# multimeter.net
KiCad netlist of a schematic drawn in EAGLE
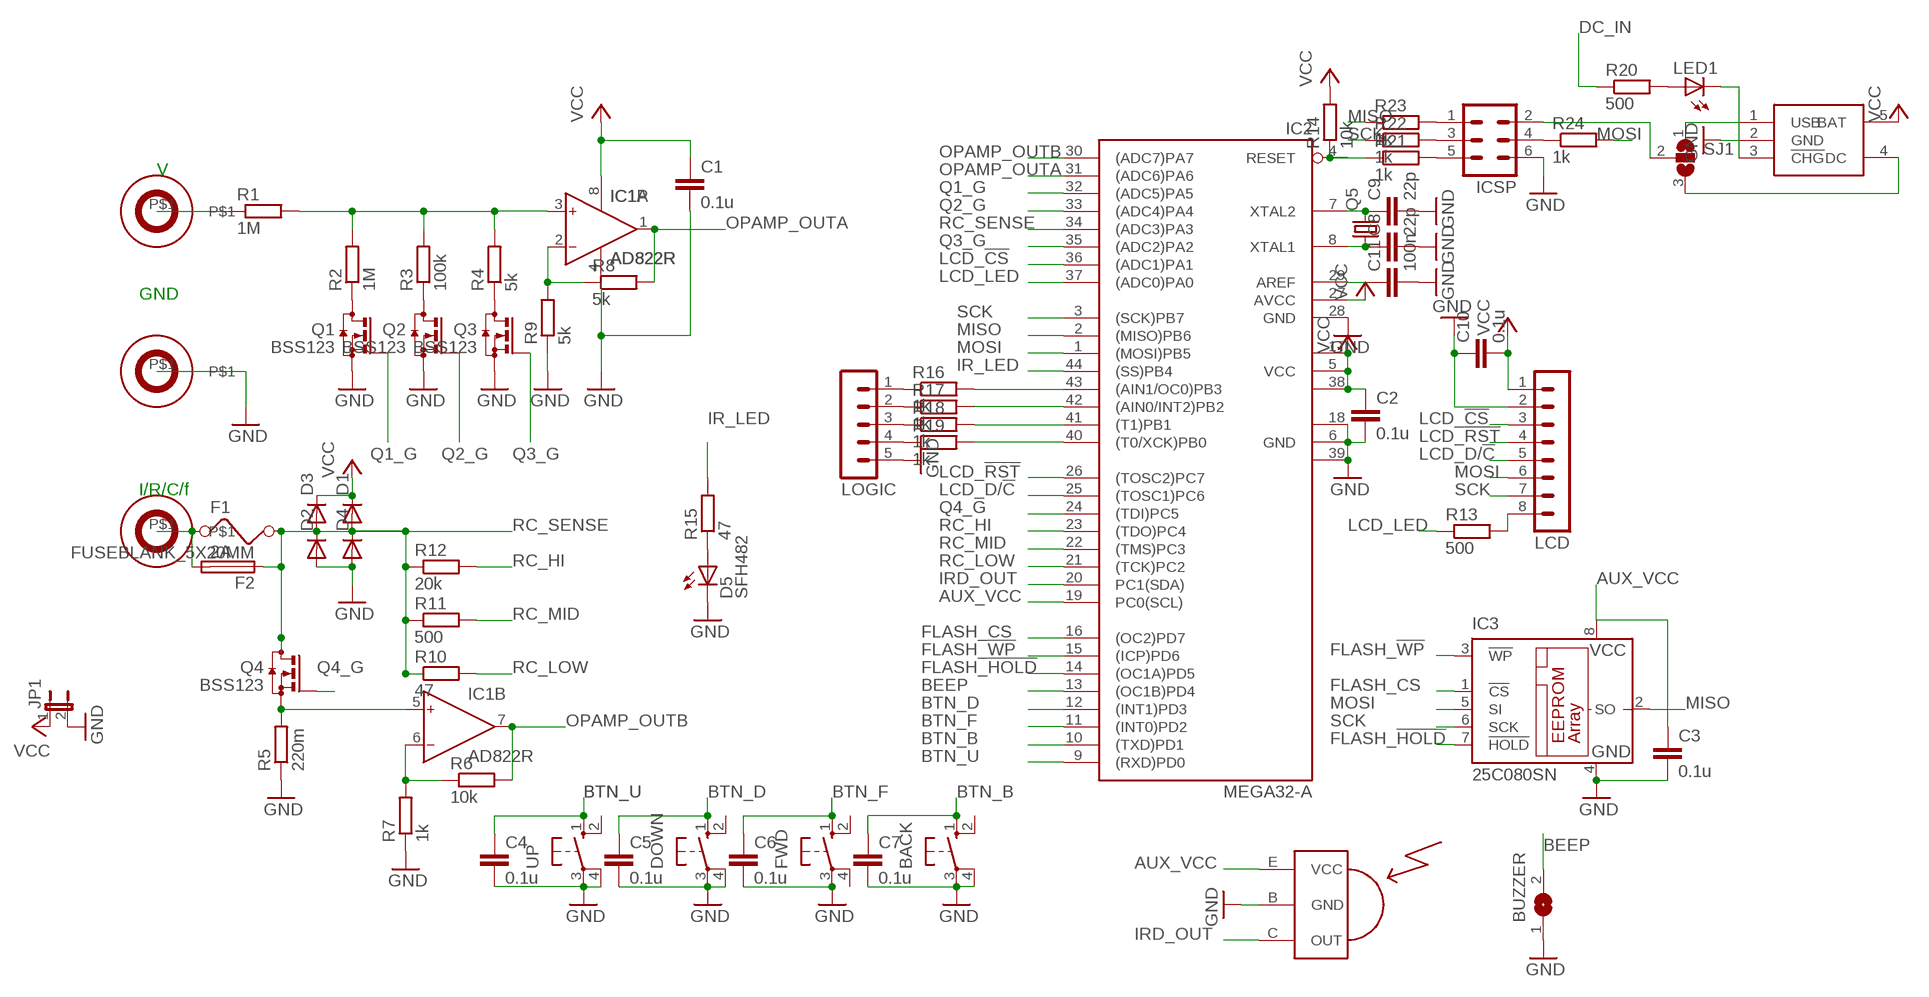
[diagram p0: schematic, sheet 1]

(export (version "E")
  (design (tool "Eeschema 10.0.6"))
  (components
    (comp (ref "BACK")
      (value "10-XX")
      (footprint "eagle-import:B3F-10XX")
      (fields (field (name "MPN") "B3F-1000"))
      (libsource (lib "eagle-import") (part "10-XX"))
    )
    (comp (ref "BUZZER")
      (value "SJW")
      (footprint "eagle-import:SJW")
      (libsource (lib "eagle-import") (part "SJW"))
    )
    (comp (ref "C1")
      (value "0.1u")
      (footprint "eagle-import:C0805")
      (libsource (lib "eagle-import") (part "C-EUC0805"))
    )
    (comp (ref "C2")
      (value "0.1u")
      (footprint "eagle-import:C0805")
      (libsource (lib "eagle-import") (part "C-EUC0805"))
    )
    (comp (ref "C3")
      (value "0.1u")
      (footprint "eagle-import:C0805")
      (libsource (lib "eagle-import") (part "C-EUC0805"))
    )
    (comp (ref "C4")
      (value "0.1u")
      (footprint "eagle-import:C0805")
      (libsource (lib "eagle-import") (part "C-EUC0805"))
    )
    (comp (ref "C5")
      (value "0.1u")
      (footprint "eagle-import:C0805")
      (libsource (lib "eagle-import") (part "C-EUC0805"))
    )
    (comp (ref "C6")
      (value "0.1u")
      (footprint "eagle-import:C0805")
      (libsource (lib "eagle-import") (part "C-EUC0805"))
    )
    (comp (ref "C7")
      (value "0.1u")
      (footprint "eagle-import:C0805")
      (libsource (lib "eagle-import") (part "C-EUC0805"))
    )
    (comp (ref "C8")
      (value "22p")
      (footprint "eagle-import:C0603")
      (libsource (lib "eagle-import") (part "C-EUC0603"))
    )
    (comp (ref "C9")
      (value "22p")
      (footprint "eagle-import:C0603")
      (libsource (lib "eagle-import") (part "C-EUC0603"))
    )
    (comp (ref "C10")
      (value "0.1u")
      (footprint "eagle-import:C0805")
      (libsource (lib "eagle-import") (part "C-EUC0805"))
    )
    (comp (ref "C11")
      (value "100n")
      (footprint "eagle-import:C0805")
      (libsource (lib "eagle-import") (part "C-EUC0805"))
    )
    (comp (ref "D1")
      (value "DIODE-SOD123")
      (footprint "eagle-import:SOD123")
      (libsource (lib "eagle-import") (part "DIODE-SOD123"))
    )
    (comp (ref "D2")
      (value "DIODE-SOD123")
      (footprint "eagle-import:SOD123")
      (libsource (lib "eagle-import") (part "DIODE-SOD123"))
    )
    (comp (ref "D3")
      (value "DIODE-SOD123")
      (footprint "eagle-import:SOD123")
      (libsource (lib "eagle-import") (part "DIODE-SOD123"))
    )
    (comp (ref "D4")
      (value "DIODE-SOD123")
      (footprint "eagle-import:SOD123")
      (libsource (lib "eagle-import") (part "DIODE-SOD123"))
    )
    (comp (ref "D5")
      (value "SFH482")
      (footprint "eagle-import:SFH482")
      (libsource (lib "eagle-import") (part "SFH482"))
    )
    (comp (ref "DOWN")
      (value "10-XX")
      (footprint "eagle-import:B3F-10XX")
      (fields (field (name "MPN") "B3F-1000"))
      (libsource (lib "eagle-import") (part "10-XX"))
    )
    (comp (ref "F1")
      (value "2A")
      (footprint "eagle-import:R1206")
      (libsource (lib "eagle-import") (part "FUSE'1206'"))
    )
    (comp (ref "F2")
      (value "FUSEBLANK_5X20MM")
      (footprint "eagle-import:FUSE_HOLDER_5X20MM")
      (libsource (lib "eagle-import") (part "FUSEBLANK_5X20MM"))
    )
    (comp (ref "FWD")
      (value "10-XX")
      (footprint "eagle-import:B3F-10XX")
      (fields (field (name "MPN") "B3F-1000"))
      (libsource (lib "eagle-import") (part "10-XX"))
    )
    (comp (ref "IC1")
      (value "AD822R")
      (footprint "eagle-import:SO8")
      (fields (field (name "MF") "ANALOG DEVICES") (field (name "MPN") "AD822BRZ"))
      (libsource (lib "eagle-import") (part "AD822R"))
    )
    (comp (ref "IC2")
      (value "MEGA32-A")
      (footprint "eagle-import:TQFP44")
      (fields (field (name "MPN") "ATMEGA32-16AU"))
      (libsource (lib "eagle-import") (part "MEGA32-A"))
    )
    (comp (ref "IC3")
      (value "25C080SN")
      (footprint "eagle-import:SO-08")
      (fields (field (name "MF") "MICROCHIP") (field (name "MPN") "25C080/SN"))
      (libsource (lib "eagle-import") (part "25SNC080"))
    )
    (comp (ref "ICSP")
      (value "MA03-2")
      (footprint "eagle-import:MA03-2")
      (libsource (lib "eagle-import") (part "MA03-2"))
    )
    (comp (ref "JP1")
      (value "JP1E")
      (footprint "eagle-import:JP1")
      (libsource (lib "eagle-import") (part "JP1E"))
    )
    (comp (ref "LCD")
      (value "MA08-1")
      (footprint "eagle-import:MA08-1")
      (libsource (lib "eagle-import") (part "MA08-1"))
    )
    (comp (ref "LED1")
      (value "LEDSML0805")
      (footprint "eagle-import:SML0805")
      (libsource (lib "eagle-import") (part "LEDSML0805"))
    )
    (comp (ref "LOGIC")
      (value "MA05-1")
      (footprint "eagle-import:MA05-1")
      (libsource (lib "eagle-import") (part "MA05-1"))
    )
    (comp (ref "N$36")
      (value "BINDINGPOST4MMPCB")
      (footprint "eagle-import:BINDINGPOSTPCB")
      (libsource (lib "eagle-import") (part "BINDINGPOST4MMPCB"))
    )
    (comp (ref "Q1")
      (value "BSS123")
      (footprint "eagle-import:SOT23")
      (libsource (lib "eagle-import") (part "BSS123"))
    )
    (comp (ref "Q2")
      (value "BSS123")
      (footprint "eagle-import:SOT23")
      (libsource (lib "eagle-import") (part "BSS123"))
    )
    (comp (ref "Q3")
      (value "BSS123")
      (footprint "eagle-import:SOT23")
      (libsource (lib "eagle-import") (part "BSS123"))
    )
    (comp (ref "Q4")
      (value "BSS123")
      (footprint "eagle-import:SOT23")
      (libsource (lib "eagle-import") (part "BSS123"))
    )
    (comp (ref "Q5")
      (value "CRYSTALHC49UP")
      (footprint "eagle-import:HC49UP")
      (libsource (lib "eagle-import") (part "CRYSTALHC49UP"))
    )
    (comp (ref "R1")
      (value "1M")
      (footprint "eagle-import:0207_12")
      (libsource (lib "eagle-import") (part "R-EU_0207/12"))
    )
    (comp (ref "R2")
      (value "1M")
      (footprint "eagle-import:R0805")
      (libsource (lib "eagle-import") (part "resistor_R-EU_R0805"))
    )
    (comp (ref "R3")
      (value "100k")
      (footprint "eagle-import:R0805")
      (libsource (lib "eagle-import") (part "resistor_R-EU_R0805"))
    )
    (comp (ref "R4")
      (value "5k")
      (footprint "eagle-import:R0805")
      (libsource (lib "eagle-import") (part "resistor_R-EU_R0805"))
    )
    (comp (ref "R5")
      (value "220m")
      (footprint "eagle-import:R1206")
      (libsource (lib "eagle-import") (part "resistor_R-EU_R1206"))
    )
    (comp (ref "R6")
      (value "10k")
      (footprint "eagle-import:R0805")
      (libsource (lib "eagle-import") (part "R-EU_R0805"))
    )
    (comp (ref "R7")
      (value "1k")
      (footprint "eagle-import:R0805")
      (libsource (lib "eagle-import") (part "R-EU_R0805"))
    )
    (comp (ref "R8")
      (value "5k")
      (footprint "eagle-import:R0805")
      (libsource (lib "eagle-import") (part "R-EU_R0805"))
    )
    (comp (ref "R9")
      (value "5k")
      (footprint "eagle-import:R0805")
      (libsource (lib "eagle-import") (part "R-EU_R0805"))
    )
    (comp (ref "R10")
      (value "47")
      (footprint "eagle-import:R0805")
      (libsource (lib "eagle-import") (part "R-EU_R0805"))
    )
    (comp (ref "R11")
      (value "500")
      (footprint "eagle-import:R0805")
      (libsource (lib "eagle-import") (part "R-EU_R0805"))
    )
    (comp (ref "R12")
      (value "20k")
      (footprint "eagle-import:R0805")
      (libsource (lib "eagle-import") (part "R-EU_R0805"))
    )
    (comp (ref "R13")
      (value "500")
      (footprint "eagle-import:R0805")
      (libsource (lib "eagle-import") (part "R-EU_R0805"))
    )
    (comp (ref "R14")
      (value "10k")
      (footprint "eagle-import:R0805")
      (libsource (lib "eagle-import") (part "R-EU_R0805"))
    )
    (comp (ref "R15")
      (value "47")
      (footprint "eagle-import:R0805")
      (libsource (lib "eagle-import") (part "R-EU_R0805"))
    )
    (comp (ref "R16")
      (value "1k")
      (footprint "eagle-import:R0805")
      (libsource (lib "eagle-import") (part "R-EU_R0805"))
    )
    (comp (ref "R17")
      (value "1k")
      (footprint "eagle-import:R0805")
      (libsource (lib "eagle-import") (part "R-EU_R0805"))
    )
    (comp (ref "R18")
      (value "1k")
      (footprint "eagle-import:R0805")
      (libsource (lib "eagle-import") (part "R-EU_R0805"))
    )
    (comp (ref "R19")
      (value "1k")
      (footprint "eagle-import:R0805")
      (libsource (lib "eagle-import") (part "R-EU_R0805"))
    )
    (comp (ref "R20")
      (value "500")
      (footprint "eagle-import:R0805")
      (libsource (lib "eagle-import") (part "R-EU_R0805"))
    )
    (comp (ref "R21")
      (value "1k")
      (footprint "eagle-import:R0805")
      (libsource (lib "eagle-import") (part "R-EU_R0805"))
    )
    (comp (ref "R22")
      (value "1k")
      (footprint "eagle-import:R0805")
      (libsource (lib "eagle-import") (part "R-EU_R0805"))
    )
    (comp (ref "R23")
      (value "1k")
      (footprint "eagle-import:R0805")
      (libsource (lib "eagle-import") (part "R-EU_R0805"))
    )
    (comp (ref "R24")
      (value "1k")
      (footprint "eagle-import:R0805")
      (libsource (lib "eagle-import") (part "R-EU_R0805"))
    )
    (comp (ref "SJ1")
      (value "SJ2W")
      (footprint "eagle-import:SJ_2")
      (libsource (lib "eagle-import") (part "SJ2W"))
    )
    (comp (ref "U$1")
      (value "BINDINGPOST4MMPCB")
      (footprint "eagle-import:BINDINGPOSTPCB")
      (libsource (lib "eagle-import") (part "BINDINGPOST4MMPCB"))
    )
    (comp (ref "U$2")
      (value "BINDINGPOST4MMPCB")
      (footprint "eagle-import:BINDINGPOSTPCB")
      (libsource (lib "eagle-import") (part "BINDINGPOST4MMPCB"))
    )
    (comp (ref "U$3")
      (value "IRDETECTOR")
      (footprint "eagle-import:TO92-EBC")
      (libsource (lib "eagle-import") (part "IRDETECTOR"))
    )
    (comp (ref "U$4")
      (value "LITHIUMCHARGER")
      (footprint "eagle-import:SOT23-5L")
      (libsource (lib "eagle-import") (part "LITHIUMCHARGER"))
    )
    (comp (ref "UP")
      (value "10-XX")
      (footprint "eagle-import:B3F-10XX")
      (fields (field (name "MPN") "B3F-1000"))
      (libsource (lib "eagle-import") (part "10-XX"))
    )
  )
  (nets
    (net (code "1") (name "/AUX_VCC") (class "Default")
      (node (ref "C3") (pin "1") (pinfunction "1_1") (pintype "passive"))
      (node (ref "IC2") (pin "19") (pinfunction "PC0(SCL)_19") (pintype "bidirectional"))
      (node (ref "IC3") (pin "8") (pinfunction "VCC_8") (pintype "power_in"))
      (node (ref "U$3") (pin "E") (pinfunction "VCC_E") (pintype "power_in"))
    )
    (net (code "2") (name "/BEEP") (class "Default")
      (node (ref "BUZZER") (pin "2") (pinfunction "2_2") (pintype "passive"))
      (node (ref "IC2") (pin "13") (pinfunction "(OC1B)PD4_13") (pintype "bidirectional"))
    )
    (net (code "3") (name "/BTN_B") (class "Default")
      (node (ref "BACK") (pin "1") (pinfunction "S_1") (pintype "passive"))
      (node (ref "C7") (pin "1") (pinfunction "1_1") (pintype "passive"))
      (node (ref "IC2") (pin "10") (pinfunction "(TXD)PD1_10") (pintype "bidirectional"))
    )
    (net (code "4") (name "/BTN_D") (class "Default")
      (node (ref "C5") (pin "1") (pinfunction "1_1") (pintype "passive"))
      (node (ref "DOWN") (pin "1") (pinfunction "S_1") (pintype "passive"))
      (node (ref "IC2") (pin "12") (pinfunction "(INT1)PD3_12") (pintype "bidirectional"))
    )
    (net (code "5") (name "/BTN_F") (class "Default")
      (node (ref "C6") (pin "1") (pinfunction "1_1") (pintype "passive"))
      (node (ref "FWD") (pin "1") (pinfunction "S_1") (pintype "passive"))
      (node (ref "IC2") (pin "11") (pinfunction "(INT0)PD2_11") (pintype "bidirectional"))
    )
    (net (code "6") (name "/BTN_U") (class "Default")
      (node (ref "C4") (pin "1") (pinfunction "1_1") (pintype "passive"))
      (node (ref "IC2") (pin "9") (pinfunction "(RXD)PD0_9") (pintype "bidirectional"))
      (node (ref "UP") (pin "1") (pinfunction "S_1") (pintype "passive"))
    )
    (net (code "7") (name "/DC_IN") (class "Default")
      (node (ref "ICSP") (pin "2") (pinfunction "2_2") (pintype "passive"))
      (node (ref "R20") (pin "1") (pinfunction "1_1") (pintype "passive"))
      (node (ref "SJ1") (pin "2") (pinfunction "2_2") (pintype "passive"))
    )
    (net (code "8") (name "/FLASH_CS") (class "Default")
      (node (ref "IC2") (pin "16") (pinfunction "(OC2)PD7_16") (pintype "bidirectional"))
      (node (ref "IC3") (pin "1") (pinfunction "~{CS}_1") (pintype "input"))
    )
    (net (code "9") (name "/FLASH_~{HOLD}") (class "Default")
      (node (ref "IC2") (pin "14") (pinfunction "(OC1A)PD5_14") (pintype "bidirectional"))
      (node (ref "IC3") (pin "7") (pinfunction "~{HOLD}_7") (pintype "input"))
    )
    (net (code "10") (name "/FLASH_~{WP}") (class "Default")
      (node (ref "IC2") (pin "15") (pinfunction "(ICP)PD6_15") (pintype "bidirectional"))
      (node (ref "IC3") (pin "3") (pinfunction "~{WP}_3") (pintype "input"))
    )
    (net (code "11") (name "/IRD_OUT") (class "Default")
      (node (ref "IC2") (pin "20") (pinfunction "PC1(SDA)_20") (pintype "bidirectional"))
      (node (ref "U$3") (pin "C") (pinfunction "OUT_C") (pintype "output"))
    )
    (net (code "12") (name "/IR_LED") (class "Default")
      (node (ref "IC2") (pin "44") (pinfunction "(SS)PB4_44") (pintype "bidirectional"))
      (node (ref "R15") (pin "2") (pinfunction "2_2") (pintype "passive"))
    )
    (net (code "13") (name "/LCD_D{slash}~{C}") (class "Default")
      (node (ref "IC2") (pin "25") (pinfunction "(TOSC1)PC6_25") (pintype "bidirectional"))
      (node (ref "LCD") (pin "5") (pinfunction "5_5") (pintype "passive"))
    )
    (net (code "14") (name "/LCD_LED") (class "Default")
      (node (ref "IC2") (pin "37") (pinfunction "(ADC0)PA0_37") (pintype "bidirectional"))
      (node (ref "R13") (pin "1") (pinfunction "1_1") (pintype "passive"))
    )
    (net (code "15") (name "/LCD_~{CS}") (class "Default")
      (node (ref "IC2") (pin "36") (pinfunction "(ADC1)PA1_36") (pintype "bidirectional"))
      (node (ref "LCD") (pin "3") (pinfunction "3_3") (pintype "passive"))
    )
    (net (code "16") (name "/LCD_~{RST}") (class "Default")
      (node (ref "IC2") (pin "26") (pinfunction "(TOSC2)PC7_26") (pintype "bidirectional"))
      (node (ref "LCD") (pin "4") (pinfunction "4_4") (pintype "passive"))
    )
    (net (code "17") (name "/MISO") (class "Default")
      (node (ref "IC2") (pin "2") (pinfunction "(MISO)PB6_2") (pintype "bidirectional"))
      (node (ref "IC3") (pin "2") (pinfunction "SO_2") (pintype "bidirectional"))
      (node (ref "R23") (pin "1") (pinfunction "1_1") (pintype "passive"))
    )
    (net (code "18") (name "/MOSI") (class "Default")
      (node (ref "IC2") (pin "1") (pinfunction "(MOSI)PB5_1") (pintype "bidirectional"))
      (node (ref "IC3") (pin "5") (pinfunction "SI_5") (pintype "input"))
      (node (ref "LCD") (pin "6") (pinfunction "6_6") (pintype "passive"))
      (node (ref "R24") (pin "2") (pinfunction "2_2") (pintype "passive"))
    )
    (net (code "19") (name "/OPAMP_OUTA") (class "Default")
      (node (ref "IC1") (pin "1") (pinfunction "OUT_1") (pintype "output"))
      (node (ref "IC2") (pin "31") (pinfunction "(ADC6)PA6_31") (pintype "bidirectional"))
      (node (ref "R8") (pin "2") (pinfunction "2_2") (pintype "passive"))
    )
    (net (code "20") (name "/OPAMP_OUTB") (class "Default")
      (node (ref "IC1") (pin "7") (pinfunction "OUT_7") (pintype "output"))
      (node (ref "IC2") (pin "30") (pinfunction "(ADC7)PA7_30") (pintype "bidirectional"))
      (node (ref "R6") (pin "2") (pinfunction "2_2") (pintype "passive"))
    )
    (net (code "21") (name "/Q1_G") (class "Default")
      (node (ref "IC2") (pin "32") (pinfunction "(ADC5)PA5_32") (pintype "bidirectional"))
      (node (ref "Q1") (pin "1") (pinfunction "G_1") (pintype "passive"))
    )
    (net (code "22") (name "/Q2_G") (class "Default")
      (node (ref "IC2") (pin "33") (pinfunction "(ADC4)PA4_33") (pintype "bidirectional"))
      (node (ref "Q2") (pin "1") (pinfunction "G_1") (pintype "passive"))
    )
    (net (code "23") (name "/Q3_G") (class "Default")
      (node (ref "IC2") (pin "35") (pinfunction "(ADC2)PA2_35") (pintype "bidirectional"))
      (node (ref "Q3") (pin "1") (pinfunction "G_1") (pintype "passive"))
    )
    (net (code "24") (name "/Q4_G") (class "Default")
      (node (ref "IC2") (pin "24") (pinfunction "(TDI)PC5_24") (pintype "bidirectional"))
      (node (ref "Q4") (pin "1") (pinfunction "G_1") (pintype "passive"))
    )
    (net (code "25") (name "/RC_HI") (class "Default")
      (node (ref "IC2") (pin "23") (pinfunction "(TDO)PC4_23") (pintype "bidirectional"))
      (node (ref "R12") (pin "2") (pinfunction "2_2") (pintype "passive"))
    )
    (net (code "26") (name "/RC_LOW") (class "Default")
      (node (ref "IC2") (pin "21") (pinfunction "(TCK)PC2_21") (pintype "bidirectional"))
      (node (ref "R10") (pin "2") (pinfunction "2_2") (pintype "passive"))
    )
    (net (code "27") (name "/RC_MID") (class "Default")
      (node (ref "IC2") (pin "22") (pinfunction "(TMS)PC3_22") (pintype "bidirectional"))
      (node (ref "R11") (pin "2") (pinfunction "2_2") (pintype "passive"))
    )
    (net (code "28") (name "/RC_SENSE") (class "Default")
      (node (ref "D1") (pin "A") (pinfunction "A_A") (pintype "passive"))
      (node (ref "D2") (pin "C") (pinfunction "C_C") (pintype "passive"))
      (node (ref "D3") (pin "A") (pinfunction "A_A") (pintype "passive"))
      (node (ref "D4") (pin "C") (pinfunction "C_C") (pintype "passive"))
      (node (ref "F1") (pin "2") (pinfunction "2_2") (pintype "passive"))
      (node (ref "F2") (pin "1") (pinfunction "1_1") (pintype "passive"))
      (node (ref "IC2") (pin "34") (pinfunction "(ADC3)PA3_34") (pintype "bidirectional"))
      (node (ref "Q4") (pin "3") (pinfunction "D_3") (pintype "passive"))
      (node (ref "R10") (pin "1") (pinfunction "1_1") (pintype "passive"))
      (node (ref "R11") (pin "1") (pinfunction "1_1") (pintype "passive"))
      (node (ref "R12") (pin "1") (pinfunction "1_1") (pintype "passive"))
    )
    (net (code "29") (name "/SCK") (class "Default")
      (node (ref "IC2") (pin "3") (pinfunction "(SCK)PB7_3") (pintype "bidirectional"))
      (node (ref "IC3") (pin "6") (pinfunction "SCK_6") (pintype "input"))
      (node (ref "LCD") (pin "7") (pinfunction "7_7") (pintype "passive"))
      (node (ref "R22") (pin "1") (pinfunction "1_1") (pintype "passive"))
    )
    (net (code "30") (name "GND") (class "Default")
      (node (ref "BACK") (pin "3") (pinfunction "P_3") (pintype "passive"))
      (node (ref "BACK") (pin "4") (pinfunction "P1_4") (pintype "passive"))
      (node (ref "BUZZER") (pin "1") (pinfunction "1_1") (pintype "passive"))
      (node (ref "C1") (pin "2") (pinfunction "2_2") (pintype "passive"))
      (node (ref "C10") (pin "1") (pinfunction "1_1") (pintype "passive"))
      (node (ref "C11") (pin "2") (pinfunction "2_2") (pintype "passive"))
      (node (ref "C2") (pin "2") (pinfunction "2_2") (pintype "passive"))
      (node (ref "C3") (pin "2") (pinfunction "2_2") (pintype "passive"))
      (node (ref "C4") (pin "2") (pinfunction "2_2") (pintype "passive"))
      (node (ref "C5") (pin "2") (pinfunction "2_2") (pintype "passive"))
      (node (ref "C6") (pin "2") (pinfunction "2_2") (pintype "passive"))
      (node (ref "C7") (pin "2") (pinfunction "2_2") (pintype "passive"))
      (node (ref "C8") (pin "2") (pinfunction "2_2") (pintype "passive"))
      (node (ref "C9") (pin "2") (pinfunction "2_2") (pintype "passive"))
      (node (ref "D2") (pin "A") (pinfunction "A_A") (pintype "passive"))
      (node (ref "D4") (pin "A") (pinfunction "A_A") (pintype "passive"))
      (node (ref "D5") (pin "K") (pinfunction "C_K") (pintype "passive"))
      (node (ref "DOWN") (pin "3") (pinfunction "P_3") (pintype "passive"))
      (node (ref "DOWN") (pin "4") (pinfunction "P1_4") (pintype "passive"))
      (node (ref "FWD") (pin "3") (pinfunction "P_3") (pintype "passive"))
      (node (ref "IC1") (pin "4") (pinfunction "V-_4") (pintype "power_in"))
      (node (ref "IC2") (pin "18") (pinfunction "GND1_18") (pintype "power_in"))
      (node (ref "IC2") (pin "28") (pinfunction "GND_28") (pintype "power_in"))
      (node (ref "IC2") (pin "39") (pinfunction "GND2_39") (pintype "power_in"))
      (node (ref "IC2") (pin "6") (pinfunction "GND_6") (pintype "power_in"))
      (node (ref "IC3") (pin "4") (pinfunction "GND_4") (pintype "power_in"))
      (node (ref "ICSP") (pin "6") (pinfunction "6_6") (pintype "passive"))
      (node (ref "JP1") (pin "2") (pinfunction "2_2") (pintype "passive"))
      (node (ref "LCD") (pin "2") (pinfunction "2_2") (pintype "passive"))
      (node (ref "LOGIC") (pin "5") (pinfunction "5_5") (pintype "passive"))
      (node (ref "Q1") (pin "2") (pinfunction "S_2") (pintype "passive"))
      (node (ref "Q2") (pin "2") (pinfunction "S_2") (pintype "passive"))
      (node (ref "Q3") (pin "2") (pinfunction "S_2") (pintype "passive"))
      (node (ref "R5") (pin "1") (pinfunction "1_1") (pintype "passive"))
      (node (ref "R7") (pin "1") (pinfunction "1_1") (pintype "passive"))
      (node (ref "R9") (pin "1") (pinfunction "1_1") (pintype "passive"))
      (node (ref "U$2") (pin "P$1") (pinfunction "P$1_P$1") (pintype "bidirectional"))
      (node (ref "U$3") (pin "B") (pinfunction "GND_B") (pintype "power_in"))
      (node (ref "U$4") (pin "2") (pinfunction "GND_2") (pintype "bidirectional"))
      (node (ref "UP") (pin "3") (pinfunction "P_3") (pintype "passive"))
      (node (ref "UP") (pin "4") (pinfunction "P1_4") (pintype "passive"))
    )
    (net (code "31") (name "Net-(D5-PadA)") (class "Default")
      (node (ref "D5") (pin "A") (pinfunction "A_A") (pintype "passive"))
      (node (ref "R15") (pin "1") (pinfunction "1_1") (pintype "passive"))
    )
    (net (code "32") (name "Net-(F1-Pad1)") (class "Default")
      (node (ref "F1") (pin "1") (pinfunction "1_1") (pintype "passive"))
      (node (ref "F2") (pin "2") (pinfunction "2_2") (pintype "passive"))
      (node (ref "N$36") (pin "P$1") (pinfunction "P$1_P$1") (pintype "bidirectional"))
    )
    (net (code "33") (name "Net-(IC1A-IN+)") (class "Default")
      (node (ref "IC1") (pin "3") (pinfunction "IN+_3") (pintype "input"))
      (node (ref "R1") (pin "2") (pinfunction "2_2") (pintype "passive"))
      (node (ref "R2") (pin "2") (pinfunction "2_2") (pintype "passive"))
      (node (ref "R3") (pin "2") (pinfunction "2_2") (pintype "passive"))
      (node (ref "R4") (pin "2") (pinfunction "2_2") (pintype "passive"))
    )
    (net (code "34") (name "Net-(IC1A-IN-)") (class "Default")
      (node (ref "IC1") (pin "2") (pinfunction "IN-_2") (pintype "input"))
      (node (ref "R8") (pin "1") (pinfunction "1_1") (pintype "passive"))
      (node (ref "R9") (pin "2") (pinfunction "2_2") (pintype "passive"))
    )
    (net (code "35") (name "Net-(IC1B-IN+)") (class "Default")
      (node (ref "IC1") (pin "5") (pinfunction "IN+_5") (pintype "input"))
      (node (ref "Q4") (pin "2") (pinfunction "S_2") (pintype "passive"))
      (node (ref "R5") (pin "2") (pinfunction "2_2") (pintype "passive"))
    )
    (net (code "36") (name "Net-(IC1B-IN-)") (class "Default")
      (node (ref "IC1") (pin "6") (pinfunction "IN-_6") (pintype "input"))
      (node (ref "R6") (pin "1") (pinfunction "1_1") (pintype "passive"))
      (node (ref "R7") (pin "2") (pinfunction "2_2") (pintype "passive"))
    )
    (net (code "37") (name "Net-(IC2-(AIN0{slash}INT2)PB2)") (class "Default")
      (node (ref "IC2") (pin "42") (pinfunction "(AIN0/INT2)PB2_42") (pintype "bidirectional"))
      (node (ref "R17") (pin "2") (pinfunction "2_2") (pintype "passive"))
    )
    (net (code "38") (name "Net-(IC2-(AIN1{slash}OC0)PB3)") (class "Default")
      (node (ref "IC2") (pin "43") (pinfunction "(AIN1/OC0)PB3_43") (pintype "bidirectional"))
      (node (ref "R16") (pin "2") (pinfunction "2_2") (pintype "passive"))
    )
    (net (code "39") (name "Net-(IC2-(T0{slash}XCK)PB0)") (class "Default")
      (node (ref "IC2") (pin "40") (pinfunction "(T0/XCK)PB0_40") (pintype "bidirectional"))
      (node (ref "R19") (pin "2") (pinfunction "2_2") (pintype "passive"))
    )
    (net (code "40") (name "Net-(IC2-(T1)PB1)") (class "Default")
      (node (ref "IC2") (pin "41") (pinfunction "(T1)PB1_41") (pintype "bidirectional"))
      (node (ref "R18") (pin "2") (pinfunction "2_2") (pintype "passive"))
    )
    (net (code "41") (name "Net-(IC2-AREF)") (class "Default")
      (node (ref "C11") (pin "1") (pinfunction "1_1") (pintype "passive"))
      (node (ref "IC2") (pin "29") (pinfunction "AREF_29") (pintype "passive"))
    )
    (net (code "42") (name "Net-(IC2-RESET)") (class "Default")
      (node (ref "IC2") (pin "4") (pinfunction "RESET_4") (pintype "input"))
      (node (ref "R14") (pin "1") (pinfunction "1_1") (pintype "passive"))
      (node (ref "R21") (pin "1") (pinfunction "1_1") (pintype "passive"))
    )
    (net (code "43") (name "Net-(IC2-XTAL1)") (class "Default")
      (node (ref "C8") (pin "1") (pinfunction "1_1") (pintype "passive"))
      (node (ref "IC2") (pin "8") (pinfunction "XTAL1_8") (pintype "bidirectional"))
      (node (ref "Q5") (pin "1") (pinfunction "1_1") (pintype "passive"))
    )
    (net (code "44") (name "Net-(IC2-XTAL2)") (class "Default")
      (node (ref "C9") (pin "1") (pinfunction "1_1") (pintype "passive"))
      (node (ref "IC2") (pin "7") (pinfunction "XTAL2_7") (pintype "bidirectional"))
      (node (ref "Q5") (pin "2") (pinfunction "2_2") (pintype "passive"))
    )
    (net (code "45") (name "Net-(ICSP-Pad1)") (class "Default")
      (node (ref "ICSP") (pin "1") (pinfunction "1_1") (pintype "passive"))
      (node (ref "R23") (pin "2") (pinfunction "2_2") (pintype "passive"))
    )
    (net (code "46") (name "Net-(ICSP-Pad3)") (class "Default")
      (node (ref "ICSP") (pin "3") (pinfunction "3_3") (pintype "passive"))
      (node (ref "R22") (pin "2") (pinfunction "2_2") (pintype "passive"))
    )
    (net (code "47") (name "Net-(ICSP-Pad4)") (class "Default")
      (node (ref "ICSP") (pin "4") (pinfunction "4_4") (pintype "passive"))
      (node (ref "R24") (pin "1") (pinfunction "1_1") (pintype "passive"))
    )
    (net (code "48") (name "Net-(ICSP-Pad5)") (class "Default")
      (node (ref "ICSP") (pin "5") (pinfunction "5_5") (pintype "passive"))
      (node (ref "R21") (pin "2") (pinfunction "2_2") (pintype "passive"))
    )
    (net (code "49") (name "Net-(LCD-Pad8)") (class "Default")
      (node (ref "LCD") (pin "8") (pinfunction "8_8") (pintype "passive"))
      (node (ref "R13") (pin "2") (pinfunction "2_2") (pintype "passive"))
    )
    (net (code "50") (name "Net-(LED1-PadA)") (class "Default")
      (node (ref "LED1") (pin "A") (pinfunction "A_A") (pintype "passive"))
      (node (ref "R20") (pin "2") (pinfunction "2_2") (pintype "passive"))
    )
    (net (code "51") (name "Net-(LOGIC-Pad1)") (class "Default")
      (node (ref "LOGIC") (pin "1") (pinfunction "1_1") (pintype "passive"))
      (node (ref "R16") (pin "1") (pinfunction "1_1") (pintype "passive"))
    )
    (net (code "52") (name "Net-(LOGIC-Pad2)") (class "Default")
      (node (ref "LOGIC") (pin "2") (pinfunction "2_2") (pintype "passive"))
      (node (ref "R17") (pin "1") (pinfunction "1_1") (pintype "passive"))
    )
    (net (code "53") (name "Net-(LOGIC-Pad3)") (class "Default")
      (node (ref "LOGIC") (pin "3") (pinfunction "3_3") (pintype "passive"))
      (node (ref "R18") (pin "1") (pinfunction "1_1") (pintype "passive"))
    )
    (net (code "54") (name "Net-(LOGIC-Pad4)") (class "Default")
      (node (ref "LOGIC") (pin "4") (pinfunction "4_4") (pintype "passive"))
      (node (ref "R19") (pin "1") (pinfunction "1_1") (pintype "passive"))
    )
    (net (code "55") (name "Net-(Q1-D)") (class "Default")
      (node (ref "Q1") (pin "3") (pinfunction "D_3") (pintype "passive"))
      (node (ref "R2") (pin "1") (pinfunction "1_1") (pintype "passive"))
    )
    (net (code "56") (name "Net-(Q2-D)") (class "Default")
      (node (ref "Q2") (pin "3") (pinfunction "D_3") (pintype "passive"))
      (node (ref "R3") (pin "1") (pinfunction "1_1") (pintype "passive"))
    )
    (net (code "57") (name "Net-(Q3-D)") (class "Default")
      (node (ref "Q3") (pin "3") (pinfunction "D_3") (pintype "passive"))
      (node (ref "R4") (pin "1") (pinfunction "1_1") (pintype "passive"))
    )
    (net (code "58") (name "Net-(R1-Pad1)") (class "Default")
      (node (ref "R1") (pin "1") (pinfunction "1_1") (pintype "passive"))
      (node (ref "U$1") (pin "P$1") (pinfunction "P$1_P$1") (pintype "bidirectional"))
    )
    (net (code "59") (name "Net-(U$4-DC)") (class "Default")
      (node (ref "SJ1") (pin "3") (pinfunction "3_3") (pintype "passive"))
      (node (ref "U$4") (pin "4") (pinfunction "DC_4") (pintype "bidirectional"))
    )
    (net (code "60") (name "Net-(U$4-USB)") (class "Default")
      (node (ref "SJ1") (pin "1") (pinfunction "1_1") (pintype "passive"))
      (node (ref "U$4") (pin "1") (pinfunction "USB_1") (pintype "bidirectional"))
    )
    (net (code "61") (name "Net-(U$4-~{CHG})") (class "Default")
      (node (ref "LED1") (pin "C") (pinfunction "C_C") (pintype "passive"))
      (node (ref "U$4") (pin "3") (pinfunction "~{CHG}_3") (pintype "bidirectional"))
    )
    (net (code "62") (name "VCC") (class "Default")
      (node (ref "C1") (pin "1") (pinfunction "1_1") (pintype "passive"))
      (node (ref "C10") (pin "2") (pinfunction "2_2") (pintype "passive"))
      (node (ref "C2") (pin "1") (pinfunction "1_1") (pintype "passive"))
      (node (ref "D1") (pin "C") (pinfunction "C_C") (pintype "passive"))
      (node (ref "D3") (pin "C") (pinfunction "C_C") (pintype "passive"))
      (node (ref "IC1") (pin "8") (pinfunction "V+_8") (pintype "power_in"))
      (node (ref "IC2") (pin "17") (pinfunction "VCC1_17") (pintype "power_in"))
      (node (ref "IC2") (pin "27") (pinfunction "AVCC_27") (pintype "power_in"))
      (node (ref "IC2") (pin "38") (pinfunction "VCC2_38") (pintype "power_in"))
      (node (ref "IC2") (pin "5") (pinfunction "VCC_5") (pintype "power_in"))
      (node (ref "JP1") (pin "1") (pinfunction "1_1") (pintype "passive"))
      (node (ref "LCD") (pin "1") (pinfunction "1_1") (pintype "passive"))
      (node (ref "R14") (pin "2") (pinfunction "2_2") (pintype "passive"))
      (node (ref "U$4") (pin "5") (pinfunction "BAT_5") (pintype "bidirectional"))
    )
    (net (code "63") (name "unconnected-(BACK-S1-Pad2)") (class "Default")
      (node (ref "BACK") (pin "2") (pinfunction "S1_2") (pintype "passive"))
    )
    (net (code "64") (name "unconnected-(DOWN-S1-Pad2)") (class "Default")
      (node (ref "DOWN") (pin "2") (pinfunction "S1_2") (pintype "passive"))
    )
    (net (code "65") (name "unconnected-(FWD-P1-Pad4)") (class "Default")
      (node (ref "FWD") (pin "4") (pinfunction "P1_4") (pintype "passive"))
    )
    (net (code "66") (name "unconnected-(FWD-S1-Pad2)") (class "Default")
      (node (ref "FWD") (pin "2") (pinfunction "S1_2") (pintype "passive"))
    )
    (net (code "67") (name "unconnected-(UP-S1-Pad2)") (class "Default")
      (node (ref "UP") (pin "2") (pinfunction "S1_2") (pintype "passive"))
    )
  )
)
